# Sensor_de_linha.net
KiCad netlist of a schematic drawn in EAGLE
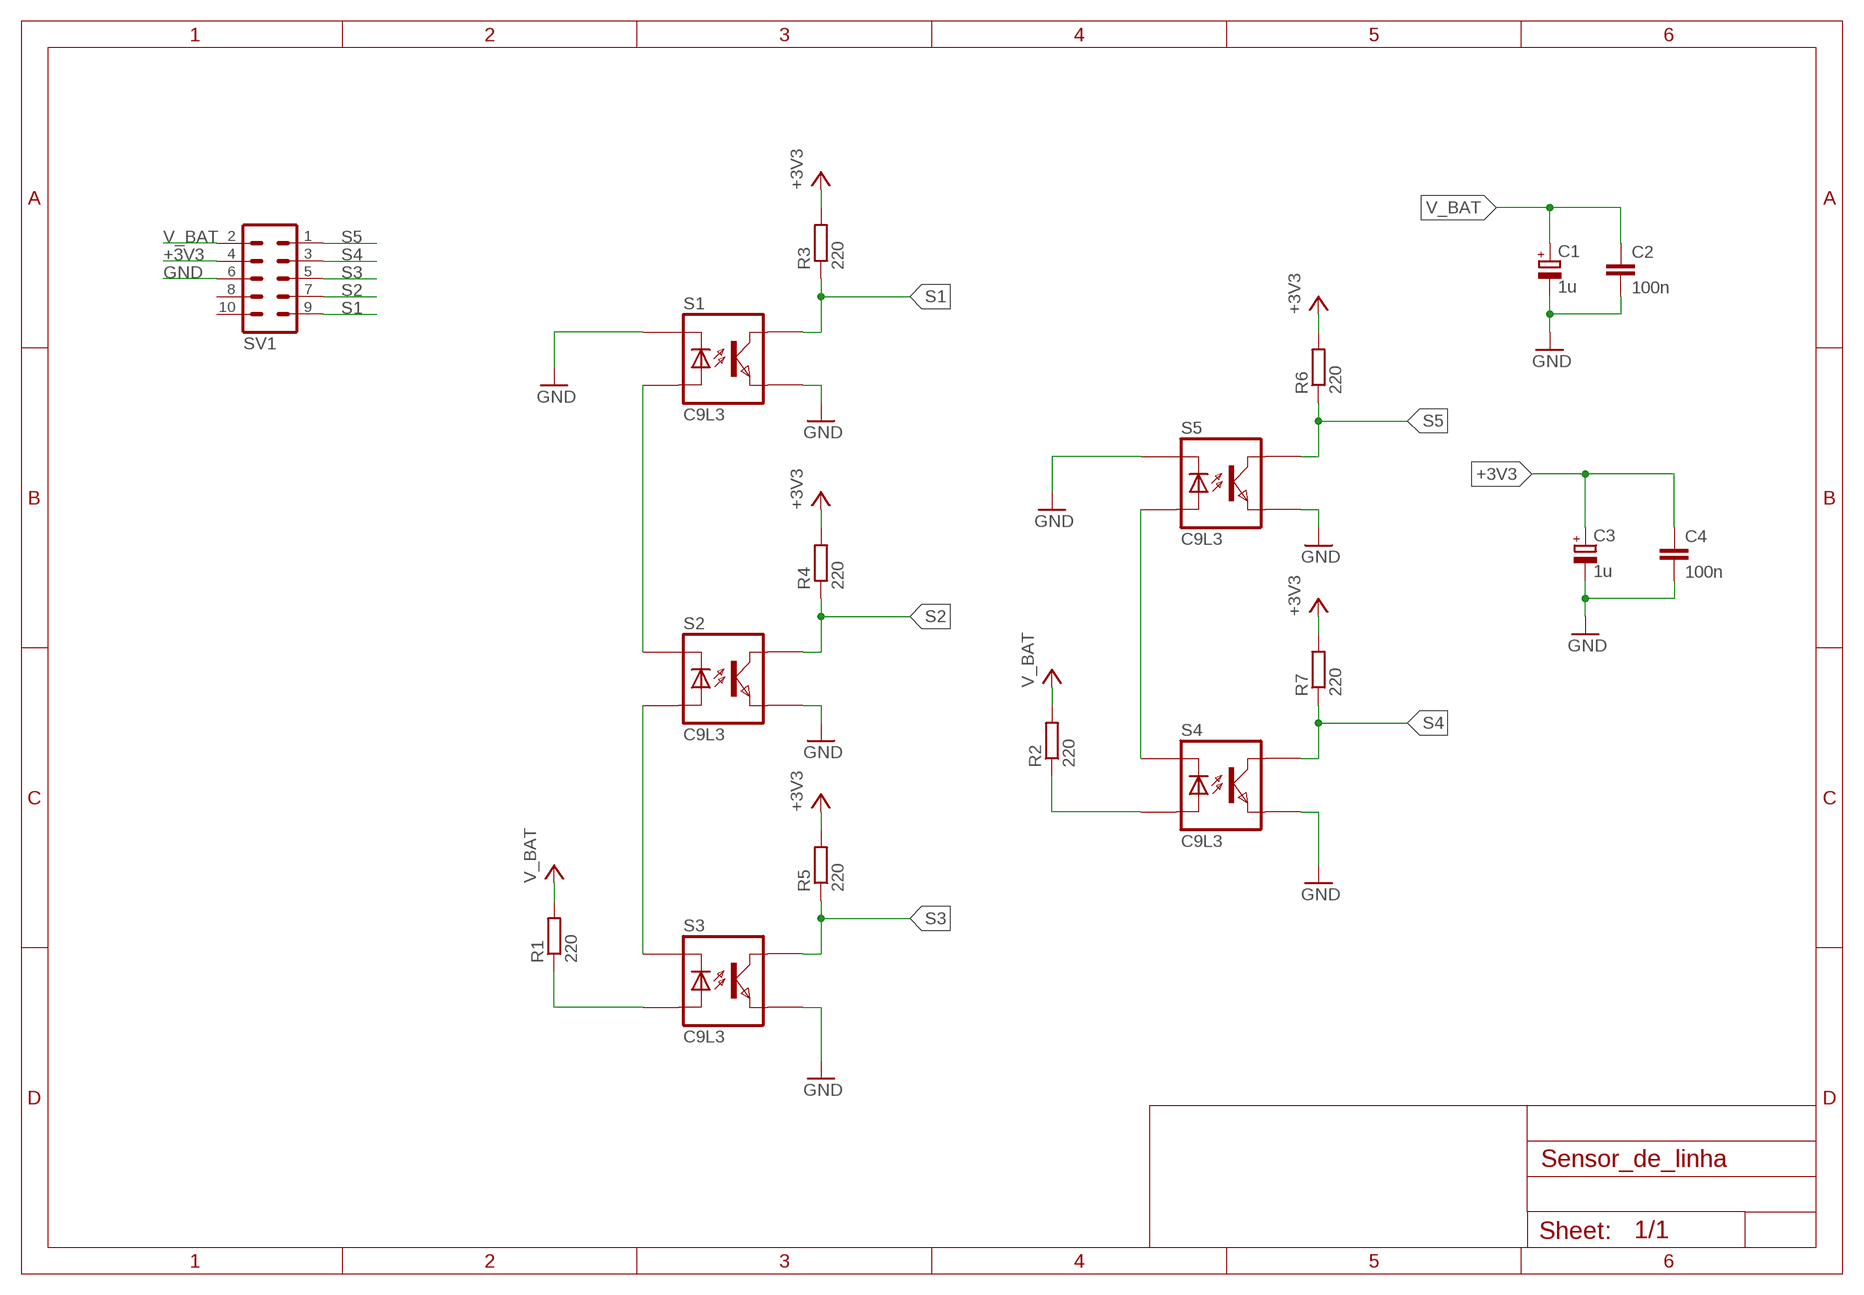
[diagram p0: schematic, sheet 1]

(export (version "E")
  (design (tool "Eeschema 10.0.6"))
  (components
    (comp (ref "C1")
      (value "1u")
      (footprint "eagle-import:E5-5")
      (libsource (lib "eagle-import") (part "CPOL-EUE5-5"))
    )
    (comp (ref "C2")
      (value "100n")
      (footprint "eagle-import:C025-030X050")
      (libsource (lib "eagle-import") (part "C-EU025-030X050"))
    )
    (comp (ref "C3")
      (value "1u")
      (footprint "eagle-import:E5-5")
      (libsource (lib "eagle-import") (part "CPOL-EUE5-5"))
    )
    (comp (ref "C4")
      (value "100n")
      (footprint "eagle-import:C025-030X050")
      (libsource (lib "eagle-import") (part "C-EU025-030X050"))
    )
    (comp (ref "R1")
      (value "220")
      (footprint "eagle-import:0204_7")
      (libsource (lib "eagle-import") (part "R-EU_0204/7"))
    )
    (comp (ref "R2")
      (value "220")
      (footprint "eagle-import:0204_7")
      (libsource (lib "eagle-import") (part "R-EU_0204/7"))
    )
    (comp (ref "R3")
      (value "220")
      (footprint "eagle-import:0204_7")
      (libsource (lib "eagle-import") (part "R-EU_0204/7"))
    )
    (comp (ref "R4")
      (value "220")
      (footprint "eagle-import:0204_7")
      (libsource (lib "eagle-import") (part "R-EU_0204/7"))
    )
    (comp (ref "R5")
      (value "220")
      (footprint "eagle-import:0204_7")
      (libsource (lib "eagle-import") (part "R-EU_0204/7"))
    )
    (comp (ref "R6")
      (value "220")
      (footprint "eagle-import:0204_7")
      (libsource (lib "eagle-import") (part "R-EU_0204/7"))
    )
    (comp (ref "R7")
      (value "220")
      (footprint "eagle-import:0204_7")
      (libsource (lib "eagle-import") (part "R-EU_0204/7"))
    )
    (comp (ref "S1")
      (value "C9L3")
      (footprint "eagle-import:C9L3")
      (libsource (lib "eagle-import") (part "C9L3"))
    )
    (comp (ref "S2")
      (value "C9L3")
      (footprint "eagle-import:C9L3")
      (libsource (lib "eagle-import") (part "C9L3"))
    )
    (comp (ref "S3")
      (value "C9L3")
      (footprint "eagle-import:C9L3")
      (libsource (lib "eagle-import") (part "C9L3"))
    )
    (comp (ref "S4")
      (value "C9L3")
      (footprint "eagle-import:C9L3")
      (libsource (lib "eagle-import") (part "C9L3"))
    )
    (comp (ref "S5")
      (value "C9L3")
      (footprint "eagle-import:C9L3")
      (libsource (lib "eagle-import") (part "C9L3"))
    )
    (comp (ref "SV1")
      (value "MA05-2")
      (footprint "eagle-import:MA05-2")
      (libsource (lib "eagle-import") (part "MA05-2"))
    )
  )
  (nets
    (net (code "1") (name "+3V3") (class "Default")
      (node (ref "C3") (pin "+") (pinfunction "+_+") (pintype "passive"))
      (node (ref "C4") (pin "1") (pinfunction "1_1") (pintype "passive"))
      (node (ref "R3") (pin "2") (pinfunction "2_2") (pintype "passive"))
      (node (ref "R4") (pin "2") (pinfunction "2_2") (pintype "passive"))
      (node (ref "R5") (pin "2") (pinfunction "2_2") (pintype "passive"))
      (node (ref "R6") (pin "2") (pinfunction "2_2") (pintype "passive"))
      (node (ref "R7") (pin "2") (pinfunction "2_2") (pintype "passive"))
      (node (ref "SV1") (pin "4") (pinfunction "4_4") (pintype "passive"))
    )
    (net (code "2") (name "GND") (class "Default")
      (node (ref "C1") (pin "-") (pinfunction "-_-") (pintype "passive"))
      (node (ref "C2") (pin "2") (pinfunction "2_2") (pintype "passive"))
      (node (ref "C3") (pin "-") (pinfunction "-_-") (pintype "passive"))
      (node (ref "C4") (pin "2") (pinfunction "2_2") (pintype "passive"))
      (node (ref "S1") (pin "2") (pinfunction "2_2") (pintype "bidirectional"))
      (node (ref "S1") (pin "4") (pinfunction "4_4") (pintype "bidirectional"))
      (node (ref "S2") (pin "2") (pinfunction "2_2") (pintype "bidirectional"))
      (node (ref "S3") (pin "2") (pinfunction "2_2") (pintype "bidirectional"))
      (node (ref "S4") (pin "2") (pinfunction "2_2") (pintype "bidirectional"))
      (node (ref "S5") (pin "2") (pinfunction "2_2") (pintype "bidirectional"))
      (node (ref "S5") (pin "4") (pinfunction "4_4") (pintype "bidirectional"))
      (node (ref "SV1") (pin "6") (pinfunction "6_6") (pintype "passive"))
    )
    (net (code "3") (name "Net-(R1-Pad1)") (class "Default")
      (node (ref "R1") (pin "1") (pinfunction "1_1") (pintype "passive"))
      (node (ref "S3") (pin "1") (pinfunction "1_1") (pintype "bidirectional"))
    )
    (net (code "4") (name "Net-(R2-Pad1)") (class "Default")
      (node (ref "R2") (pin "1") (pinfunction "1_1") (pintype "passive"))
      (node (ref "S4") (pin "1") (pinfunction "1_1") (pintype "bidirectional"))
    )
    (net (code "5") (name "Net-(S1-Pad1)") (class "Default")
      (node (ref "S1") (pin "1") (pinfunction "1_1") (pintype "bidirectional"))
      (node (ref "S2") (pin "4") (pinfunction "4_4") (pintype "bidirectional"))
    )
    (net (code "6") (name "Net-(S2-Pad1)") (class "Default")
      (node (ref "S2") (pin "1") (pinfunction "1_1") (pintype "bidirectional"))
      (node (ref "S3") (pin "4") (pinfunction "4_4") (pintype "bidirectional"))
    )
    (net (code "7") (name "Net-(S4-Pad4)") (class "Default")
      (node (ref "S4") (pin "4") (pinfunction "4_4") (pintype "bidirectional"))
      (node (ref "S5") (pin "1") (pinfunction "1_1") (pintype "bidirectional"))
    )
    (net (code "8") (name "S1") (class "Default")
      (node (ref "R3") (pin "1") (pinfunction "1_1") (pintype "passive"))
      (node (ref "S1") (pin "3") (pinfunction "3_3") (pintype "bidirectional"))
      (node (ref "SV1") (pin "9") (pinfunction "9_9") (pintype "passive"))
    )
    (net (code "9") (name "S2") (class "Default")
      (node (ref "R4") (pin "1") (pinfunction "1_1") (pintype "passive"))
      (node (ref "S2") (pin "3") (pinfunction "3_3") (pintype "bidirectional"))
      (node (ref "SV1") (pin "7") (pinfunction "7_7") (pintype "passive"))
    )
    (net (code "10") (name "S3") (class "Default")
      (node (ref "R5") (pin "1") (pinfunction "1_1") (pintype "passive"))
      (node (ref "S3") (pin "3") (pinfunction "3_3") (pintype "bidirectional"))
      (node (ref "SV1") (pin "5") (pinfunction "5_5") (pintype "passive"))
    )
    (net (code "11") (name "S4") (class "Default")
      (node (ref "R7") (pin "1") (pinfunction "1_1") (pintype "passive"))
      (node (ref "S4") (pin "3") (pinfunction "3_3") (pintype "bidirectional"))
      (node (ref "SV1") (pin "3") (pinfunction "3_3") (pintype "passive"))
    )
    (net (code "12") (name "S5") (class "Default")
      (node (ref "R6") (pin "1") (pinfunction "1_1") (pintype "passive"))
      (node (ref "S5") (pin "3") (pinfunction "3_3") (pintype "bidirectional"))
      (node (ref "SV1") (pin "1") (pinfunction "1_1") (pintype "passive"))
    )
    (net (code "13") (name "V_BAT") (class "Default")
      (node (ref "C1") (pin "+") (pinfunction "+_+") (pintype "passive"))
      (node (ref "C2") (pin "1") (pinfunction "1_1") (pintype "passive"))
      (node (ref "R1") (pin "2") (pinfunction "2_2") (pintype "passive"))
      (node (ref "R2") (pin "2") (pinfunction "2_2") (pintype "passive"))
      (node (ref "SV1") (pin "2") (pinfunction "2_2") (pintype "passive"))
    )
    (net (code "14") (name "unconnected-(SV1-Pad8)") (class "Default")
      (node (ref "SV1") (pin "8") (pinfunction "8_8") (pintype "passive"))
    )
    (net (code "15") (name "unconnected-(SV1-Pad10)") (class "Default")
      (node (ref "SV1") (pin "10") (pinfunction "10_10") (pintype "passive"))
    )
  )
)
